# Puzzle_Hall_Sensor_v0_9b.net
KiCad netlist of a schematic drawn in EAGLE
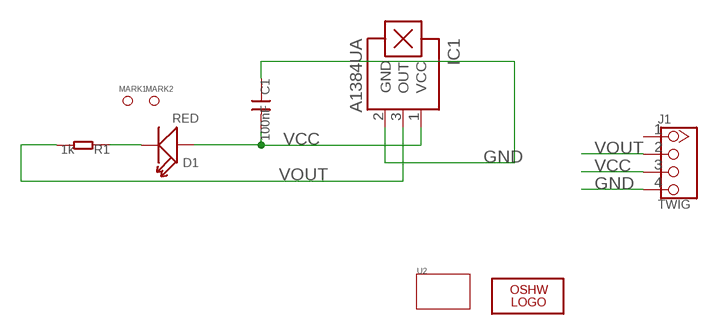
[diagram p0: schematic, sheet 1]

(export (version "E")
  (design (tool "Eeschema 10.0.6"))
  (components
    (comp (ref "C1")
      (value "100nF")
      (footprint "eagle-import:0603")
      (libsource (lib "eagle-import") (part "C-0603"))
    )
    (comp (ref "D1")
      (value "RED")
      (footprint "eagle-import:D0603")
      (libsource (lib "eagle-import") (part "LED-0603"))
    )
    (comp (ref "IC1")
      (value "A1384UA")
      (footprint "eagle-import:SIP3-UA")
      (fields (field (name "MPN") "A1384LUA-T"))
      (libsource (lib "eagle-import") (part "A13?UA84"))
    )
    (comp (ref "J1")
      (value "TWIG")
      (footprint "eagle-import:4P-LEADED-2.0")
      (libsource (lib "eagle-import") (part "TWIG-2.0-LEADED-2.0"))
    )
    (comp (ref "LOGO1")
      (value "LOGO-OSHW-FILLX0150-NT")
      (footprint "eagle-import:OSHW_FILLX150_NOTEXT")
      (libsource (lib "eagle-import") (part "LOGO-OSHW-FILLX0150-NT"))
    )
    (comp (ref "MARK1")
      (value "PAD-MARK")
      (footprint "eagle-import:ROUND-MARK-0.635")
      (libsource (lib "eagle-import") (part "PAD-MARK"))
    )
    (comp (ref "MARK2")
      (value "PAD-MARK")
      (footprint "eagle-import:ROUND-MARK-0.635")
      (libsource (lib "eagle-import") (part "PAD-MARK"))
    )
    (comp (ref "R1")
      (value "1k")
      (footprint "eagle-import:0603")
      (libsource (lib "eagle-import") (part "R-0603"))
    )
    (comp (ref "U2")
      (value "TWIG-1U")
      (footprint "eagle-import:1U-DIM-W_-DRILL")
      (libsource (lib "eagle-import") (part "TWIG-1U"))
    )
  )
  (nets
    (net (code "1") (name "/GND") (class "Default")
      (node (ref "C1") (pin "1") (pinfunction "1_1") (pintype "passive"))
      (node (ref "IC1") (pin "2") (pinfunction "GND_2") (pintype "power_in"))
      (node (ref "J1") (pin "4") (pinfunction "4_4") (pintype "bidirectional"))
    )
    (net (code "2") (name "/VCC") (class "Default")
      (node (ref "C1") (pin "2") (pinfunction "2_2") (pintype "passive"))
      (node (ref "D1") (pin "+") (pinfunction "+_+") (pintype "passive"))
      (node (ref "IC1") (pin "1") (pinfunction "VCC_1") (pintype "power_in"))
      (node (ref "J1") (pin "3") (pinfunction "3_3") (pintype "bidirectional"))
    )
    (net (code "3") (name "/VOUT") (class "Default")
      (node (ref "IC1") (pin "3") (pinfunction "OUT_3") (pintype "output"))
      (node (ref "J1") (pin "2") (pinfunction "2_2") (pintype "bidirectional"))
      (node (ref "R1") (pin "2") (pinfunction "2_2") (pintype "passive"))
    )
    (net (code "4") (name "Net-(D1-Pad-)") (class "Default")
      (node (ref "D1") (pin "-") (pinfunction "-_-") (pintype "passive"))
      (node (ref "R1") (pin "1") (pinfunction "1_1") (pintype "passive"))
    )
    (net (code "5") (name "unconnected-(J1-Pad1)") (class "Default")
      (node (ref "J1") (pin "1") (pinfunction "1_1") (pintype "bidirectional"))
    )
  )
)
